# invader_asyn_bridge.net
KiCad netlist of a schematic drawn in EAGLE
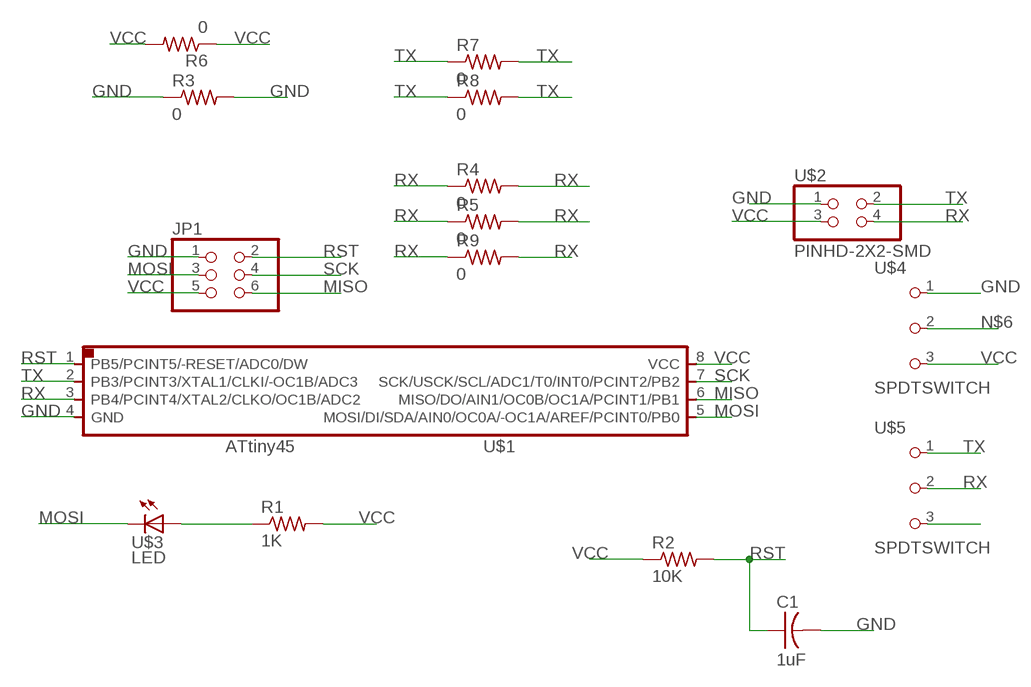
[diagram p0: schematic, sheet 1]

(export (version "E")
  (design (tool "Eeschema 10.0.6"))
  (components
    (comp (ref "C1")
      (value "1uF")
      (footprint "eagle-import:C1206FAB")
      (libsource (lib "eagle-import") (part "CAP-US1206FAB"))
    )
    (comp (ref "JP1")
      (value "PINHD-2X3-SMD")
      (footprint "eagle-import:2X03SMD")
      (libsource (lib "eagle-import") (part "PINHD-2X3-SMD"))
    )
    (comp (ref "R1")
      (value "1K")
      (footprint "eagle-import:R1206")
      (libsource (lib "eagle-import") (part "RES-US1206"))
    )
    (comp (ref "R2")
      (value "10K")
      (footprint "eagle-import:R1206")
      (libsource (lib "eagle-import") (part "RES-US1206"))
    )
    (comp (ref "R3")
      (value "0")
      (footprint "eagle-import:R1206")
      (libsource (lib "eagle-import") (part "RES-US1206"))
    )
    (comp (ref "R4")
      (value "0")
      (footprint "eagle-import:R1206")
      (libsource (lib "eagle-import") (part "RES-US1206"))
    )
    (comp (ref "R5")
      (value "0")
      (footprint "eagle-import:R1206")
      (libsource (lib "eagle-import") (part "RES-US1206"))
    )
    (comp (ref "R6")
      (value "0")
      (footprint "eagle-import:R1206")
      (libsource (lib "eagle-import") (part "RES-US1206"))
    )
    (comp (ref "R7")
      (value "0")
      (footprint "eagle-import:R1206")
      (libsource (lib "eagle-import") (part "RES-US1206"))
    )
    (comp (ref "R8")
      (value "0")
      (footprint "eagle-import:R1206")
      (libsource (lib "eagle-import") (part "RES-US1206"))
    )
    (comp (ref "R9")
      (value "0")
      (footprint "eagle-import:R1206")
      (libsource (lib "eagle-import") (part "RES-US1206"))
    )
    (comp (ref "U$1")
      (value "ATTINY45SI")
      (footprint "eagle-import:SOIC8")
      (libsource (lib "eagle-import") (part "ATTINY45SI"))
    )
    (comp (ref "U$2")
      (value "PINHD-2X2-SMD")
      (footprint "eagle-import:2X02SMD")
      (libsource (lib "eagle-import") (part "PINHD-2X2-SMD"))
    )
    (comp (ref "U$3")
      (value "LED")
      (footprint "eagle-import:LED1206FAB")
      (libsource (lib "eagle-import") (part "LEDFAB1206"))
    )
    (comp (ref "U$4")
      (value "SPDTSWITCH")
      (footprint "eagle-import:SPDTSWITCH")
      (libsource (lib "eagle-import") (part "SPDTSWITCH"))
    )
    (comp (ref "U$5")
      (value "SPDTSWITCH")
      (footprint "eagle-import:SPDTSWITCH")
      (libsource (lib "eagle-import") (part "SPDTSWITCH"))
    )
  )
  (nets
    (net (code "1") (name "/GND") (class "Default")
      (node (ref "C1") (pin "2") (pinfunction "2_2") (pintype "passive"))
      (node (ref "JP1") (pin "1") (pinfunction "1_1") (pintype "passive"))
      (node (ref "R3") (pin "1") (pinfunction "1_1") (pintype "passive"))
      (node (ref "R3") (pin "2") (pinfunction "2_2") (pintype "passive"))
      (node (ref "U$1") (pin "4") (pinfunction "GND_4") (pintype "bidirectional"))
      (node (ref "U$2") (pin "1") (pinfunction "1_1") (pintype "passive"))
      (node (ref "U$4") (pin "1") (pinfunction "1_1") (pintype "passive"))
    )
    (net (code "2") (name "/MISO") (class "Default")
      (node (ref "JP1") (pin "6") (pinfunction "6_6") (pintype "passive"))
      (node (ref "U$1") (pin "6") (pinfunction "MISO/DO/AIN1/OC0B/OC1A/PCINT1/PB1_6") (pintype "bidirectional"))
    )
    (net (code "3") (name "/MOSI") (class "Default")
      (node (ref "JP1") (pin "3") (pinfunction "3_3") (pintype "passive"))
      (node (ref "U$1") (pin "5") (pinfunction "MOSI/DI/SDA/AIN0/OC0A/-OC1A/AREF/PCINT0/PB0_5") (pintype "bidirectional"))
      (node (ref "U$3") (pin "2") (pinfunction "C_2") (pintype "passive"))
    )
    (net (code "4") (name "/N$6") (class "Default")
      (node (ref "U$4") (pin "2") (pinfunction "2_2") (pintype "passive"))
    )
    (net (code "5") (name "/RST") (class "Default")
      (node (ref "C1") (pin "1") (pinfunction "1_1") (pintype "passive"))
      (node (ref "JP1") (pin "2") (pinfunction "2_2") (pintype "passive"))
      (node (ref "R2") (pin "2") (pinfunction "2_2") (pintype "passive"))
      (node (ref "U$1") (pin "1") (pinfunction "PB5/PCINT5/-RESET/ADC0/DW_1") (pintype "bidirectional"))
    )
    (net (code "6") (name "/RX") (class "Default")
      (node (ref "R4") (pin "1") (pinfunction "1_1") (pintype "passive"))
      (node (ref "R4") (pin "2") (pinfunction "2_2") (pintype "passive"))
      (node (ref "R5") (pin "1") (pinfunction "1_1") (pintype "passive"))
      (node (ref "R5") (pin "2") (pinfunction "2_2") (pintype "passive"))
      (node (ref "R9") (pin "1") (pinfunction "1_1") (pintype "passive"))
      (node (ref "R9") (pin "2") (pinfunction "2_2") (pintype "passive"))
      (node (ref "U$1") (pin "3") (pinfunction "PB4/PCINT4/XTAL2/CLKO/OC1B/ADC2_3") (pintype "bidirectional"))
      (node (ref "U$2") (pin "4") (pinfunction "4_4") (pintype "passive"))
      (node (ref "U$5") (pin "2") (pinfunction "2_2") (pintype "passive"))
    )
    (net (code "7") (name "/SCK") (class "Default")
      (node (ref "JP1") (pin "4") (pinfunction "4_4") (pintype "passive"))
      (node (ref "U$1") (pin "7") (pinfunction "SCK/USCK/SCL/ADC1/T0/INT0/PCINT2/PB2_7") (pintype "bidirectional"))
    )
    (net (code "8") (name "/TX") (class "Default")
      (node (ref "R7") (pin "1") (pinfunction "1_1") (pintype "passive"))
      (node (ref "R7") (pin "2") (pinfunction "2_2") (pintype "passive"))
      (node (ref "R8") (pin "1") (pinfunction "1_1") (pintype "passive"))
      (node (ref "R8") (pin "2") (pinfunction "2_2") (pintype "passive"))
      (node (ref "U$1") (pin "2") (pinfunction "PB3/PCINT3/XTAL1/CLKI/-OC1B/ADC3_2") (pintype "bidirectional"))
      (node (ref "U$2") (pin "2") (pinfunction "2_2") (pintype "passive"))
      (node (ref "U$5") (pin "1") (pinfunction "1_1") (pintype "passive"))
    )
    (net (code "9") (name "/VCC") (class "Default")
      (node (ref "JP1") (pin "5") (pinfunction "5_5") (pintype "passive"))
      (node (ref "R1") (pin "2") (pinfunction "2_2") (pintype "passive"))
      (node (ref "R2") (pin "1") (pinfunction "1_1") (pintype "passive"))
      (node (ref "R6") (pin "1") (pinfunction "1_1") (pintype "passive"))
      (node (ref "R6") (pin "2") (pinfunction "2_2") (pintype "passive"))
      (node (ref "U$1") (pin "8") (pinfunction "VCC_8") (pintype "bidirectional"))
      (node (ref "U$2") (pin "3") (pinfunction "3_3") (pintype "passive"))
      (node (ref "U$4") (pin "3") (pinfunction "3_3") (pintype "passive"))
    )
    (net (code "10") (name "Net-(U$3-A)") (class "Default")
      (node (ref "R1") (pin "1") (pinfunction "1_1") (pintype "passive"))
      (node (ref "U$3") (pin "1") (pinfunction "A_1") (pintype "passive"))
    )
    (net (code "11") (name "unconnected-(U$5-Pad3)") (class "Default")
      (node (ref "U$5") (pin "3") (pinfunction "3_3") (pintype "passive"))
    )
  )
)
